# reg.net
KiCad netlist of a schematic drawn in EAGLE
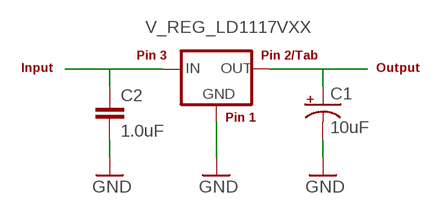
[diagram p0: schematic, sheet 1]

(export (version "E")
  (design (tool "Eeschema 10.0.6"))
  (components
    (comp (ref "C1")
      (value "10uF")
      (footprint "eagle-import:EIA3216")
      (libsource (lib "eagle-import") (part "10UF-16V-10%(TANT)"))
    )
    (comp (ref "C2")
      (value "1.0uF")
      (footprint "eagle-import:0603-CAP")
      (libsource (lib "eagle-import") (part "1.0UF-16V-10%(0603)"))
    )
    (comp (ref "U$1")
      (value "V_REG_LD1117VXX")
      (footprint "eagle-import:78XXL")
      (libsource (lib "eagle-import") (part "V_REG_LD1117VXX"))
    )
  )
  (nets
    (net (code "1") (name "GND") (class "Default")
      (node (ref "C1") (pin "C") (pinfunction "-_C") (pintype "passive"))
      (node (ref "C2") (pin "2") (pinfunction "2_2") (pintype "passive"))
      (node (ref "U$1") (pin "IN") (pinfunction "GND_IN") (pintype "input"))
    )
    (net (code "2") (name "Net-(C1-+)") (class "Default")
      (node (ref "C1") (pin "A") (pinfunction "+_A") (pintype "passive"))
      (node (ref "U$1") (pin "GND") (pinfunction "OUT_GND") (pintype "passive"))
    )
    (net (code "3") (name "Net-(U$1-IN)") (class "Default")
      (node (ref "C2") (pin "1") (pinfunction "1_1") (pintype "passive"))
      (node (ref "U$1") (pin "OUT") (pinfunction "IN_OUT") (pintype "input"))
    )
  )
)
